# RotaryEncoder_connection.net
KiCad netlist of a schematic drawn in Altium Designer
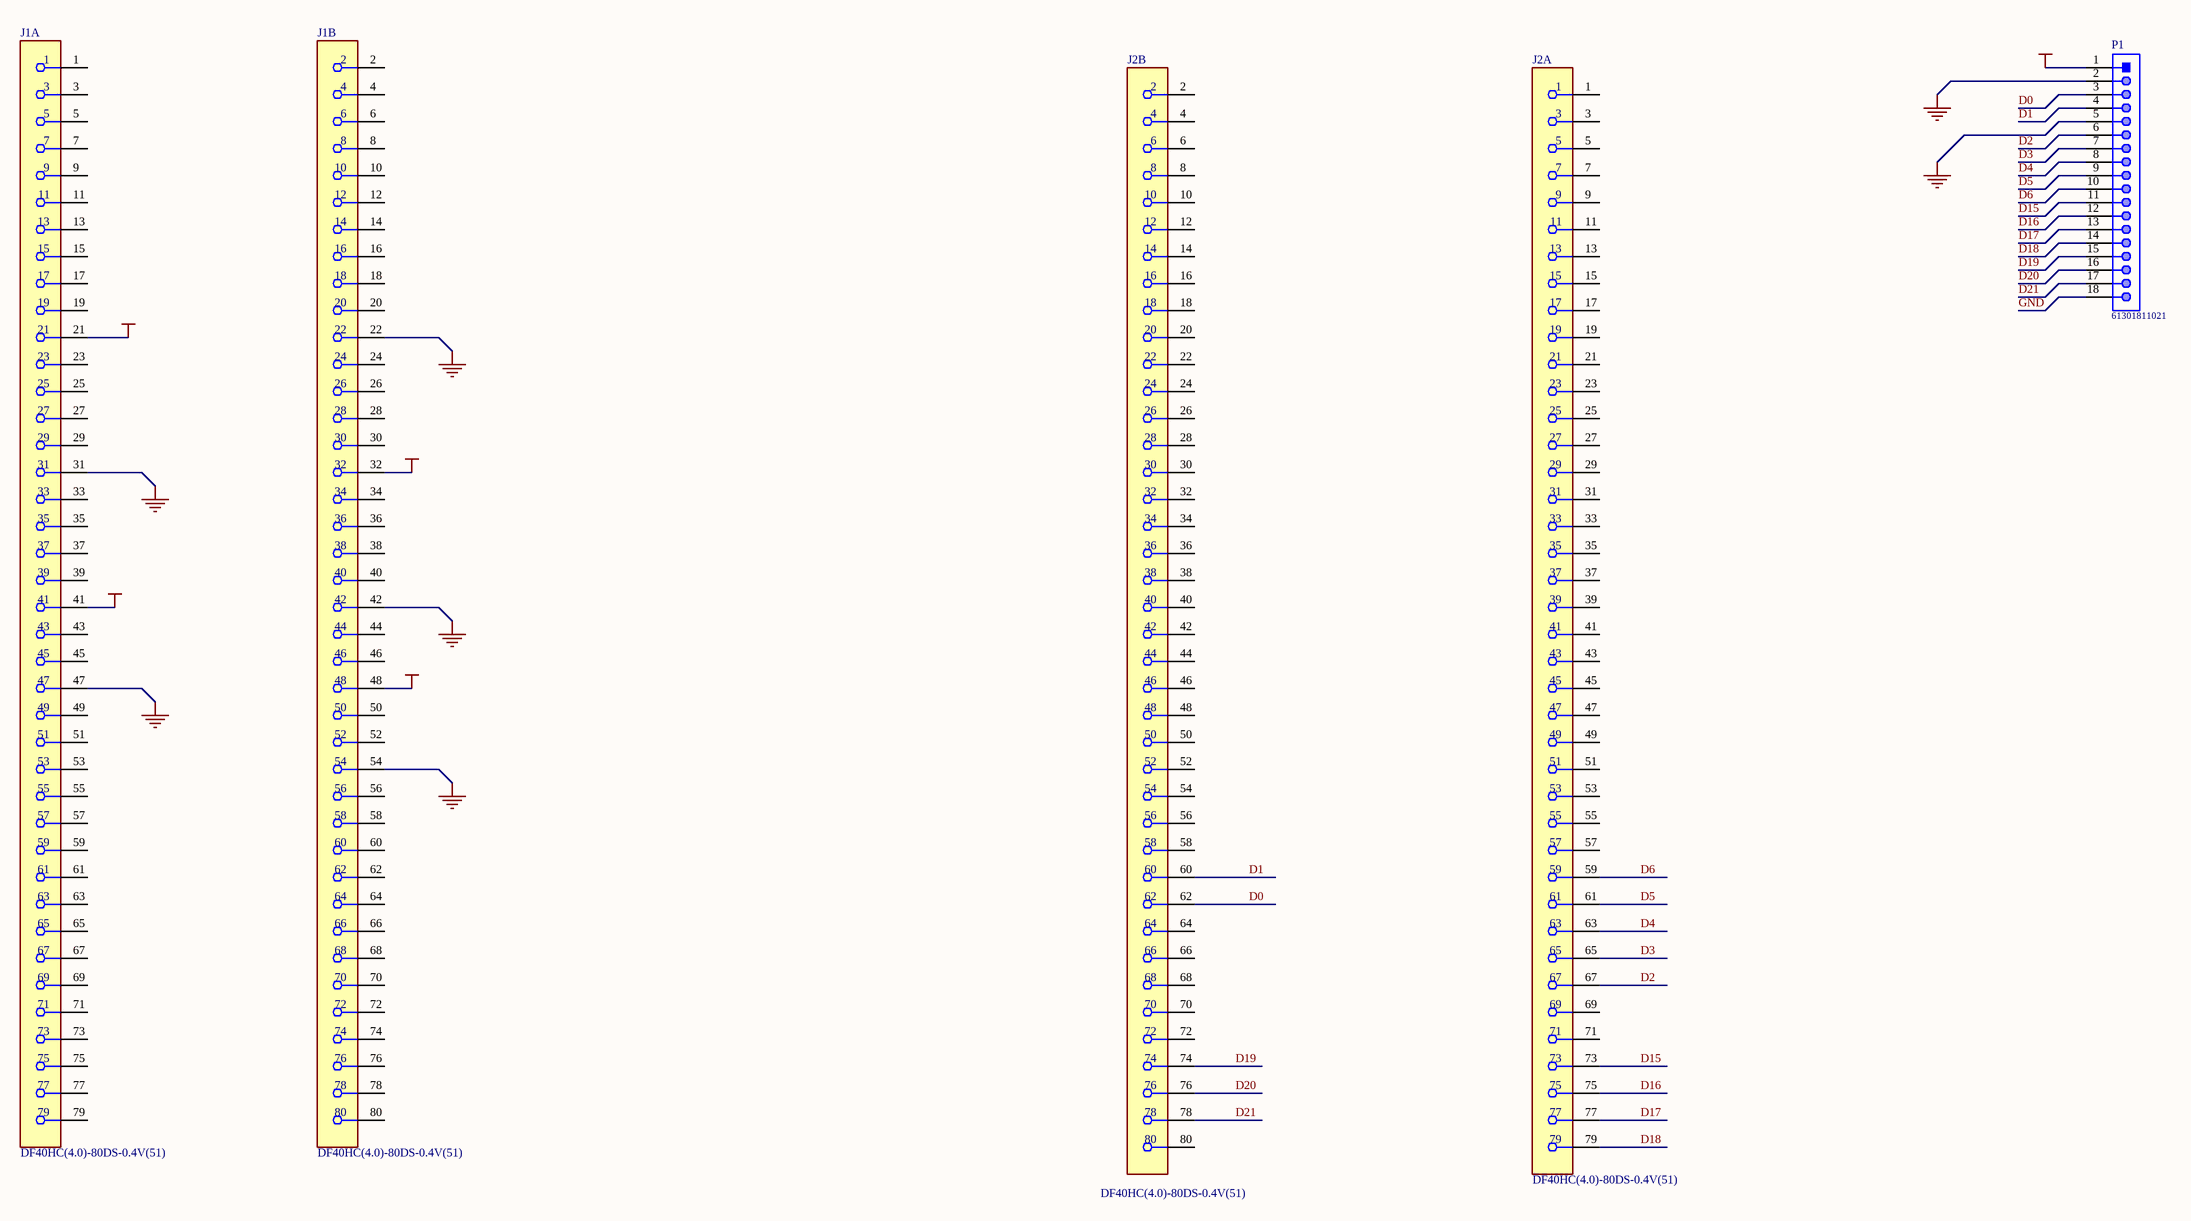
[diagram p0: RotaryEncoder_connection.SchDoc]

(export (version "E")
  (design (tool "Eeschema 10.0.6"))
  (components
    (comp (ref "J1")
      (value "DF40HC(4.0)-80DS-0.4V(51)")
      (footprint "FP-DF40HC_4_0_-80DS-0_4V-MFG")
      (description "CONN RCPT 80POS SMD GOLD")
      (fields
        (field (name "OCTOPART") "https://octopart.com/df40hc%284.0%29-80ds-0.4v%2851%29-hirose-19677719")
        (field (name "MANUFACTURER") "Hirose")
      )
      (libsource (lib "Altium Content Vault") (part "d23b9ca91198f74e05fc9b3cd90b74d"))
    )
    (comp (ref "J2")
      (value "DF40HC(4.0)-80DS-0.4V(51)")
      (footprint "FP-DF40HC_4_0_-80DS-0_4V-MFG")
      (description "CONN RCPT 80POS SMD GOLD")
      (fields
        (field (name "OCTOPART") "https://octopart.com/df40hc%284.0%29-80ds-0.4v%2851%29-hirose-19677719")
        (field (name "MANUFACTURER") "Hirose")
      )
      (libsource (lib "Altium Content Vault") (part "d23b9ca91198f74e05fc9b3cd90b74d"))
    )
    (comp (ref "P1")
      (value "61301811021")
      (footprint "61301811021")
      (description "THT Angled Pin Header WR-PHD, Pitch 2.54 mm, Single Row, 18 pins")
      (fields (field (name "MANUFACTURER") "Wurth Elektronik") (field (name "PUBLISHER") "WurthElektronik"))
      (libsource (lib "Altium Content Vault") (part "WE-CN-1P-M-R18"))
    )
  )
  (nets
    (net (code "1") (name "+5") (class "Default")
      (node (ref "J1") (pin "21") (pinfunction "21_21") (pintype "passive"))
      (node (ref "J1") (pin "32") (pinfunction "32_32") (pintype "passive"))
      (node (ref "J1") (pin "41") (pinfunction "41_41") (pintype "passive"))
      (node (ref "J1") (pin "48") (pinfunction "48_48") (pintype "passive"))
      (node (ref "P1") (pin "1") (pinfunction "1_1") (pintype "passive"))
    )
    (net (code "2") (name "/D0") (class "Default")
      (node (ref "J2") (pin "62") (pinfunction "62_62") (pintype "passive"))
      (node (ref "P1") (pin "3") (pinfunction "3_3") (pintype "passive"))
    )
    (net (code "3") (name "/D1") (class "Default")
      (node (ref "J2") (pin "60") (pinfunction "60_60") (pintype "passive"))
      (node (ref "P1") (pin "4") (pinfunction "4_4") (pintype "passive"))
    )
    (net (code "4") (name "/D2") (class "Default")
      (node (ref "J2") (pin "67") (pinfunction "67_67") (pintype "passive"))
      (node (ref "P1") (pin "6") (pinfunction "6_6") (pintype "passive"))
    )
    (net (code "5") (name "/D3") (class "Default")
      (node (ref "J2") (pin "65") (pinfunction "65_65") (pintype "passive"))
      (node (ref "P1") (pin "7") (pinfunction "7_7") (pintype "passive"))
    )
    (net (code "6") (name "/D4") (class "Default")
      (node (ref "J2") (pin "63") (pinfunction "63_63") (pintype "passive"))
      (node (ref "P1") (pin "8") (pinfunction "8_8") (pintype "passive"))
    )
    (net (code "7") (name "/D5") (class "Default")
      (node (ref "J2") (pin "61") (pinfunction "61_61") (pintype "passive"))
      (node (ref "P1") (pin "9") (pinfunction "9_9") (pintype "passive"))
    )
    (net (code "8") (name "/D6") (class "Default")
      (node (ref "J2") (pin "59") (pinfunction "59_59") (pintype "passive"))
      (node (ref "P1") (pin "10") (pinfunction "10_10") (pintype "passive"))
    )
    (net (code "9") (name "/D15") (class "Default")
      (node (ref "J2") (pin "73") (pinfunction "73_73") (pintype "passive"))
      (node (ref "P1") (pin "11") (pinfunction "11_11") (pintype "passive"))
    )
    (net (code "10") (name "/D16") (class "Default")
      (node (ref "J2") (pin "75") (pinfunction "75_75") (pintype "passive"))
      (node (ref "P1") (pin "12") (pinfunction "12_12") (pintype "passive"))
    )
    (net (code "11") (name "/D17") (class "Default")
      (node (ref "J2") (pin "77") (pinfunction "77_77") (pintype "passive"))
      (node (ref "P1") (pin "13") (pinfunction "13_13") (pintype "passive"))
    )
    (net (code "12") (name "/D18") (class "Default")
      (node (ref "J2") (pin "79") (pinfunction "79_79") (pintype "passive"))
      (node (ref "P1") (pin "14") (pinfunction "14_14") (pintype "passive"))
    )
    (net (code "13") (name "/D19") (class "Default")
      (node (ref "J2") (pin "74") (pinfunction "74_74") (pintype "passive"))
      (node (ref "P1") (pin "15") (pinfunction "15_15") (pintype "passive"))
    )
    (net (code "14") (name "/D20") (class "Default")
      (node (ref "J2") (pin "76") (pinfunction "76_76") (pintype "passive"))
      (node (ref "P1") (pin "16") (pinfunction "16_16") (pintype "passive"))
    )
    (net (code "15") (name "/D21") (class "Default")
      (node (ref "J2") (pin "78") (pinfunction "78_78") (pintype "passive"))
      (node (ref "P1") (pin "17") (pinfunction "17_17") (pintype "passive"))
    )
    (net (code "16") (name "GND") (class "Default")
      (node (ref "J1") (pin "22") (pinfunction "22_22") (pintype "passive"))
      (node (ref "J1") (pin "31") (pinfunction "31_31") (pintype "passive"))
      (node (ref "J1") (pin "42") (pinfunction "42_42") (pintype "passive"))
      (node (ref "J1") (pin "47") (pinfunction "47_47") (pintype "passive"))
      (node (ref "J1") (pin "54") (pinfunction "54_54") (pintype "passive"))
      (node (ref "P1") (pin "18") (pinfunction "18_18") (pintype "passive"))
      (node (ref "P1") (pin "2") (pinfunction "2_2") (pintype "passive"))
      (node (ref "P1") (pin "5") (pinfunction "5_5") (pintype "passive"))
    )
    (net (code "17") (name "unconnected-(J1-Pad1)") (class "Default")
      (node (ref "J1") (pin "1") (pinfunction "1_1") (pintype "passive"))
    )
    (net (code "18") (name "unconnected-(J1-Pad2)") (class "Default")
      (node (ref "J1") (pin "2") (pinfunction "2_2") (pintype "passive"))
    )
    (net (code "19") (name "unconnected-(J1-Pad3)") (class "Default")
      (node (ref "J1") (pin "3") (pinfunction "3_3") (pintype "passive"))
    )
    (net (code "20") (name "unconnected-(J1-Pad4)") (class "Default")
      (node (ref "J1") (pin "4") (pinfunction "4_4") (pintype "passive"))
    )
    (net (code "21") (name "unconnected-(J1-Pad5)") (class "Default")
      (node (ref "J1") (pin "5") (pinfunction "5_5") (pintype "passive"))
    )
    (net (code "22") (name "unconnected-(J1-Pad6)") (class "Default")
      (node (ref "J1") (pin "6") (pinfunction "6_6") (pintype "passive"))
    )
    (net (code "23") (name "unconnected-(J1-Pad7)") (class "Default")
      (node (ref "J1") (pin "7") (pinfunction "7_7") (pintype "passive"))
    )
    (net (code "24") (name "unconnected-(J1-Pad8)") (class "Default")
      (node (ref "J1") (pin "8") (pinfunction "8_8") (pintype "passive"))
    )
    (net (code "25") (name "unconnected-(J1-Pad9)") (class "Default")
      (node (ref "J1") (pin "9") (pinfunction "9_9") (pintype "passive"))
    )
    (net (code "26") (name "unconnected-(J1-Pad10)") (class "Default")
      (node (ref "J1") (pin "10") (pinfunction "10_10") (pintype "passive"))
    )
    (net (code "27") (name "unconnected-(J1-Pad11)") (class "Default")
      (node (ref "J1") (pin "11") (pinfunction "11_11") (pintype "passive"))
    )
    (net (code "28") (name "unconnected-(J1-Pad12)") (class "Default")
      (node (ref "J1") (pin "12") (pinfunction "12_12") (pintype "passive"))
    )
    (net (code "29") (name "unconnected-(J1-Pad13)") (class "Default")
      (node (ref "J1") (pin "13") (pinfunction "13_13") (pintype "passive"))
    )
    (net (code "30") (name "unconnected-(J1-Pad14)") (class "Default")
      (node (ref "J1") (pin "14") (pinfunction "14_14") (pintype "passive"))
    )
    (net (code "31") (name "unconnected-(J1-Pad15)") (class "Default")
      (node (ref "J1") (pin "15") (pinfunction "15_15") (pintype "passive"))
    )
    (net (code "32") (name "unconnected-(J1-Pad16)") (class "Default")
      (node (ref "J1") (pin "16") (pinfunction "16_16") (pintype "passive"))
    )
    (net (code "33") (name "unconnected-(J1-Pad17)") (class "Default")
      (node (ref "J1") (pin "17") (pinfunction "17_17") (pintype "passive"))
    )
    (net (code "34") (name "unconnected-(J1-Pad18)") (class "Default")
      (node (ref "J1") (pin "18") (pinfunction "18_18") (pintype "passive"))
    )
    (net (code "35") (name "unconnected-(J1-Pad19)") (class "Default")
      (node (ref "J1") (pin "19") (pinfunction "19_19") (pintype "passive"))
    )
    (net (code "36") (name "unconnected-(J1-Pad20)") (class "Default")
      (node (ref "J1") (pin "20") (pinfunction "20_20") (pintype "passive"))
    )
    (net (code "37") (name "unconnected-(J1-Pad23)") (class "Default")
      (node (ref "J1") (pin "23") (pinfunction "23_23") (pintype "passive"))
    )
    (net (code "38") (name "unconnected-(J1-Pad24)") (class "Default")
      (node (ref "J1") (pin "24") (pinfunction "24_24") (pintype "passive"))
    )
    (net (code "39") (name "unconnected-(J1-Pad25)") (class "Default")
      (node (ref "J1") (pin "25") (pinfunction "25_25") (pintype "passive"))
    )
    (net (code "40") (name "unconnected-(J1-Pad26)") (class "Default")
      (node (ref "J1") (pin "26") (pinfunction "26_26") (pintype "passive"))
    )
    (net (code "41") (name "unconnected-(J1-Pad27)") (class "Default")
      (node (ref "J1") (pin "27") (pinfunction "27_27") (pintype "passive"))
    )
    (net (code "42") (name "unconnected-(J1-Pad28)") (class "Default")
      (node (ref "J1") (pin "28") (pinfunction "28_28") (pintype "passive"))
    )
    (net (code "43") (name "unconnected-(J1-Pad29)") (class "Default")
      (node (ref "J1") (pin "29") (pinfunction "29_29") (pintype "passive"))
    )
    (net (code "44") (name "unconnected-(J1-Pad30)") (class "Default")
      (node (ref "J1") (pin "30") (pinfunction "30_30") (pintype "passive"))
    )
    (net (code "45") (name "unconnected-(J1-Pad33)") (class "Default")
      (node (ref "J1") (pin "33") (pinfunction "33_33") (pintype "passive"))
    )
    (net (code "46") (name "unconnected-(J1-Pad34)") (class "Default")
      (node (ref "J1") (pin "34") (pinfunction "34_34") (pintype "passive"))
    )
    (net (code "47") (name "unconnected-(J1-Pad35)") (class "Default")
      (node (ref "J1") (pin "35") (pinfunction "35_35") (pintype "passive"))
    )
    (net (code "48") (name "unconnected-(J1-Pad36)") (class "Default")
      (node (ref "J1") (pin "36") (pinfunction "36_36") (pintype "passive"))
    )
    (net (code "49") (name "unconnected-(J1-Pad37)") (class "Default")
      (node (ref "J1") (pin "37") (pinfunction "37_37") (pintype "passive"))
    )
    (net (code "50") (name "unconnected-(J1-Pad38)") (class "Default")
      (node (ref "J1") (pin "38") (pinfunction "38_38") (pintype "passive"))
    )
    (net (code "51") (name "unconnected-(J1-Pad39)") (class "Default")
      (node (ref "J1") (pin "39") (pinfunction "39_39") (pintype "passive"))
    )
    (net (code "52") (name "unconnected-(J1-Pad40)") (class "Default")
      (node (ref "J1") (pin "40") (pinfunction "40_40") (pintype "passive"))
    )
    (net (code "53") (name "unconnected-(J1-Pad43)") (class "Default")
      (node (ref "J1") (pin "43") (pinfunction "43_43") (pintype "passive"))
    )
    (net (code "54") (name "unconnected-(J1-Pad44)") (class "Default")
      (node (ref "J1") (pin "44") (pinfunction "44_44") (pintype "passive"))
    )
    (net (code "55") (name "unconnected-(J1-Pad45)") (class "Default")
      (node (ref "J1") (pin "45") (pinfunction "45_45") (pintype "passive"))
    )
    (net (code "56") (name "unconnected-(J1-Pad46)") (class "Default")
      (node (ref "J1") (pin "46") (pinfunction "46_46") (pintype "passive"))
    )
    (net (code "57") (name "unconnected-(J1-Pad49)") (class "Default")
      (node (ref "J1") (pin "49") (pinfunction "49_49") (pintype "passive"))
    )
    (net (code "58") (name "unconnected-(J1-Pad50)") (class "Default")
      (node (ref "J1") (pin "50") (pinfunction "50_50") (pintype "passive"))
    )
    (net (code "59") (name "unconnected-(J1-Pad51)") (class "Default")
      (node (ref "J1") (pin "51") (pinfunction "51_51") (pintype "passive"))
    )
    (net (code "60") (name "unconnected-(J1-Pad52)") (class "Default")
      (node (ref "J1") (pin "52") (pinfunction "52_52") (pintype "passive"))
    )
    (net (code "61") (name "unconnected-(J1-Pad53)") (class "Default")
      (node (ref "J1") (pin "53") (pinfunction "53_53") (pintype "passive"))
    )
    (net (code "62") (name "unconnected-(J1-Pad55)") (class "Default")
      (node (ref "J1") (pin "55") (pinfunction "55_55") (pintype "passive"))
    )
    (net (code "63") (name "unconnected-(J1-Pad56)") (class "Default")
      (node (ref "J1") (pin "56") (pinfunction "56_56") (pintype "passive"))
    )
    (net (code "64") (name "unconnected-(J1-Pad57)") (class "Default")
      (node (ref "J1") (pin "57") (pinfunction "57_57") (pintype "passive"))
    )
    (net (code "65") (name "unconnected-(J1-Pad58)") (class "Default")
      (node (ref "J1") (pin "58") (pinfunction "58_58") (pintype "passive"))
    )
    (net (code "66") (name "unconnected-(J1-Pad59)") (class "Default")
      (node (ref "J1") (pin "59") (pinfunction "59_59") (pintype "passive"))
    )
    (net (code "67") (name "unconnected-(J1-Pad60)") (class "Default")
      (node (ref "J1") (pin "60") (pinfunction "60_60") (pintype "passive"))
    )
    (net (code "68") (name "unconnected-(J1-Pad61)") (class "Default")
      (node (ref "J1") (pin "61") (pinfunction "61_61") (pintype "passive"))
    )
    (net (code "69") (name "unconnected-(J1-Pad62)") (class "Default")
      (node (ref "J1") (pin "62") (pinfunction "62_62") (pintype "passive"))
    )
    (net (code "70") (name "unconnected-(J1-Pad63)") (class "Default")
      (node (ref "J1") (pin "63") (pinfunction "63_63") (pintype "passive"))
    )
    (net (code "71") (name "unconnected-(J1-Pad64)") (class "Default")
      (node (ref "J1") (pin "64") (pinfunction "64_64") (pintype "passive"))
    )
    (net (code "72") (name "unconnected-(J1-Pad65)") (class "Default")
      (node (ref "J1") (pin "65") (pinfunction "65_65") (pintype "passive"))
    )
    (net (code "73") (name "unconnected-(J1-Pad66)") (class "Default")
      (node (ref "J1") (pin "66") (pinfunction "66_66") (pintype "passive"))
    )
    (net (code "74") (name "unconnected-(J1-Pad67)") (class "Default")
      (node (ref "J1") (pin "67") (pinfunction "67_67") (pintype "passive"))
    )
    (net (code "75") (name "unconnected-(J1-Pad68)") (class "Default")
      (node (ref "J1") (pin "68") (pinfunction "68_68") (pintype "passive"))
    )
    (net (code "76") (name "unconnected-(J1-Pad69)") (class "Default")
      (node (ref "J1") (pin "69") (pinfunction "69_69") (pintype "passive"))
    )
    (net (code "77") (name "unconnected-(J1-Pad70)") (class "Default")
      (node (ref "J1") (pin "70") (pinfunction "70_70") (pintype "passive"))
    )
    (net (code "78") (name "unconnected-(J1-Pad71)") (class "Default")
      (node (ref "J1") (pin "71") (pinfunction "71_71") (pintype "passive"))
    )
    (net (code "79") (name "unconnected-(J1-Pad72)") (class "Default")
      (node (ref "J1") (pin "72") (pinfunction "72_72") (pintype "passive"))
    )
    (net (code "80") (name "unconnected-(J1-Pad73)") (class "Default")
      (node (ref "J1") (pin "73") (pinfunction "73_73") (pintype "passive"))
    )
    (net (code "81") (name "unconnected-(J1-Pad74)") (class "Default")
      (node (ref "J1") (pin "74") (pinfunction "74_74") (pintype "passive"))
    )
    (net (code "82") (name "unconnected-(J1-Pad75)") (class "Default")
      (node (ref "J1") (pin "75") (pinfunction "75_75") (pintype "passive"))
    )
    (net (code "83") (name "unconnected-(J1-Pad76)") (class "Default")
      (node (ref "J1") (pin "76") (pinfunction "76_76") (pintype "passive"))
    )
    (net (code "84") (name "unconnected-(J1-Pad77)") (class "Default")
      (node (ref "J1") (pin "77") (pinfunction "77_77") (pintype "passive"))
    )
    (net (code "85") (name "unconnected-(J1-Pad78)") (class "Default")
      (node (ref "J1") (pin "78") (pinfunction "78_78") (pintype "passive"))
    )
    (net (code "86") (name "unconnected-(J1-Pad79)") (class "Default")
      (node (ref "J1") (pin "79") (pinfunction "79_79") (pintype "passive"))
    )
    (net (code "87") (name "unconnected-(J1-Pad80)") (class "Default")
      (node (ref "J1") (pin "80") (pinfunction "80_80") (pintype "passive"))
    )
    (net (code "88") (name "unconnected-(J2-Pad1)") (class "Default")
      (node (ref "J2") (pin "1") (pinfunction "1_1") (pintype "passive"))
    )
    (net (code "89") (name "unconnected-(J2-Pad2)") (class "Default")
      (node (ref "J2") (pin "2") (pinfunction "2_2") (pintype "passive"))
    )
    (net (code "90") (name "unconnected-(J2-Pad3)") (class "Default")
      (node (ref "J2") (pin "3") (pinfunction "3_3") (pintype "passive"))
    )
    (net (code "91") (name "unconnected-(J2-Pad4)") (class "Default")
      (node (ref "J2") (pin "4") (pinfunction "4_4") (pintype "passive"))
    )
    (net (code "92") (name "unconnected-(J2-Pad5)") (class "Default")
      (node (ref "J2") (pin "5") (pinfunction "5_5") (pintype "passive"))
    )
    (net (code "93") (name "unconnected-(J2-Pad6)") (class "Default")
      (node (ref "J2") (pin "6") (pinfunction "6_6") (pintype "passive"))
    )
    (net (code "94") (name "unconnected-(J2-Pad7)") (class "Default")
      (node (ref "J2") (pin "7") (pinfunction "7_7") (pintype "passive"))
    )
    (net (code "95") (name "unconnected-(J2-Pad8)") (class "Default")
      (node (ref "J2") (pin "8") (pinfunction "8_8") (pintype "passive"))
    )
    (net (code "96") (name "unconnected-(J2-Pad9)") (class "Default")
      (node (ref "J2") (pin "9") (pinfunction "9_9") (pintype "passive"))
    )
    (net (code "97") (name "unconnected-(J2-Pad10)") (class "Default")
      (node (ref "J2") (pin "10") (pinfunction "10_10") (pintype "passive"))
    )
    (net (code "98") (name "unconnected-(J2-Pad11)") (class "Default")
      (node (ref "J2") (pin "11") (pinfunction "11_11") (pintype "passive"))
    )
    (net (code "99") (name "unconnected-(J2-Pad12)") (class "Default")
      (node (ref "J2") (pin "12") (pinfunction "12_12") (pintype "passive"))
    )
    (net (code "100") (name "unconnected-(J2-Pad13)") (class "Default")
      (node (ref "J2") (pin "13") (pinfunction "13_13") (pintype "passive"))
    )
    (net (code "101") (name "unconnected-(J2-Pad14)") (class "Default")
      (node (ref "J2") (pin "14") (pinfunction "14_14") (pintype "passive"))
    )
    (net (code "102") (name "unconnected-(J2-Pad15)") (class "Default")
      (node (ref "J2") (pin "15") (pinfunction "15_15") (pintype "passive"))
    )
    (net (code "103") (name "unconnected-(J2-Pad16)") (class "Default")
      (node (ref "J2") (pin "16") (pinfunction "16_16") (pintype "passive"))
    )
    (net (code "104") (name "unconnected-(J2-Pad17)") (class "Default")
      (node (ref "J2") (pin "17") (pinfunction "17_17") (pintype "passive"))
    )
    (net (code "105") (name "unconnected-(J2-Pad18)") (class "Default")
      (node (ref "J2") (pin "18") (pinfunction "18_18") (pintype "passive"))
    )
    (net (code "106") (name "unconnected-(J2-Pad19)") (class "Default")
      (node (ref "J2") (pin "19") (pinfunction "19_19") (pintype "passive"))
    )
    (net (code "107") (name "unconnected-(J2-Pad20)") (class "Default")
      (node (ref "J2") (pin "20") (pinfunction "20_20") (pintype "passive"))
    )
    (net (code "108") (name "unconnected-(J2-Pad21)") (class "Default")
      (node (ref "J2") (pin "21") (pinfunction "21_21") (pintype "passive"))
    )
    (net (code "109") (name "unconnected-(J2-Pad22)") (class "Default")
      (node (ref "J2") (pin "22") (pinfunction "22_22") (pintype "passive"))
    )
    (net (code "110") (name "unconnected-(J2-Pad23)") (class "Default")
      (node (ref "J2") (pin "23") (pinfunction "23_23") (pintype "passive"))
    )
    (net (code "111") (name "unconnected-(J2-Pad24)") (class "Default")
      (node (ref "J2") (pin "24") (pinfunction "24_24") (pintype "passive"))
    )
    (net (code "112") (name "unconnected-(J2-Pad25)") (class "Default")
      (node (ref "J2") (pin "25") (pinfunction "25_25") (pintype "passive"))
    )
    (net (code "113") (name "unconnected-(J2-Pad26)") (class "Default")
      (node (ref "J2") (pin "26") (pinfunction "26_26") (pintype "passive"))
    )
    (net (code "114") (name "unconnected-(J2-Pad27)") (class "Default")
      (node (ref "J2") (pin "27") (pinfunction "27_27") (pintype "passive"))
    )
    (net (code "115") (name "unconnected-(J2-Pad28)") (class "Default")
      (node (ref "J2") (pin "28") (pinfunction "28_28") (pintype "passive"))
    )
    (net (code "116") (name "unconnected-(J2-Pad29)") (class "Default")
      (node (ref "J2") (pin "29") (pinfunction "29_29") (pintype "passive"))
    )
    (net (code "117") (name "unconnected-(J2-Pad30)") (class "Default")
      (node (ref "J2") (pin "30") (pinfunction "30_30") (pintype "passive"))
    )
    (net (code "118") (name "unconnected-(J2-Pad31)") (class "Default")
      (node (ref "J2") (pin "31") (pinfunction "31_31") (pintype "passive"))
    )
    (net (code "119") (name "unconnected-(J2-Pad32)") (class "Default")
      (node (ref "J2") (pin "32") (pinfunction "32_32") (pintype "passive"))
    )
    (net (code "120") (name "unconnected-(J2-Pad33)") (class "Default")
      (node (ref "J2") (pin "33") (pinfunction "33_33") (pintype "passive"))
    )
    (net (code "121") (name "unconnected-(J2-Pad34)") (class "Default")
      (node (ref "J2") (pin "34") (pinfunction "34_34") (pintype "passive"))
    )
    (net (code "122") (name "unconnected-(J2-Pad35)") (class "Default")
      (node (ref "J2") (pin "35") (pinfunction "35_35") (pintype "passive"))
    )
    (net (code "123") (name "unconnected-(J2-Pad36)") (class "Default")
      (node (ref "J2") (pin "36") (pinfunction "36_36") (pintype "passive"))
    )
    (net (code "124") (name "unconnected-(J2-Pad37)") (class "Default")
      (node (ref "J2") (pin "37") (pinfunction "37_37") (pintype "passive"))
    )
    (net (code "125") (name "unconnected-(J2-Pad38)") (class "Default")
      (node (ref "J2") (pin "38") (pinfunction "38_38") (pintype "passive"))
    )
    (net (code "126") (name "unconnected-(J2-Pad39)") (class "Default")
      (node (ref "J2") (pin "39") (pinfunction "39_39") (pintype "passive"))
    )
    (net (code "127") (name "unconnected-(J2-Pad40)") (class "Default")
      (node (ref "J2") (pin "40") (pinfunction "40_40") (pintype "passive"))
    )
    (net (code "128") (name "unconnected-(J2-Pad41)") (class "Default")
      (node (ref "J2") (pin "41") (pinfunction "41_41") (pintype "passive"))
    )
    (net (code "129") (name "unconnected-(J2-Pad42)") (class "Default")
      (node (ref "J2") (pin "42") (pinfunction "42_42") (pintype "passive"))
    )
    (net (code "130") (name "unconnected-(J2-Pad43)") (class "Default")
      (node (ref "J2") (pin "43") (pinfunction "43_43") (pintype "passive"))
    )
    (net (code "131") (name "unconnected-(J2-Pad44)") (class "Default")
      (node (ref "J2") (pin "44") (pinfunction "44_44") (pintype "passive"))
    )
    (net (code "132") (name "unconnected-(J2-Pad45)") (class "Default")
      (node (ref "J2") (pin "45") (pinfunction "45_45") (pintype "passive"))
    )
    (net (code "133") (name "unconnected-(J2-Pad46)") (class "Default")
      (node (ref "J2") (pin "46") (pinfunction "46_46") (pintype "passive"))
    )
    (net (code "134") (name "unconnected-(J2-Pad47)") (class "Default")
      (node (ref "J2") (pin "47") (pinfunction "47_47") (pintype "passive"))
    )
    (net (code "135") (name "unconnected-(J2-Pad48)") (class "Default")
      (node (ref "J2") (pin "48") (pinfunction "48_48") (pintype "passive"))
    )
    (net (code "136") (name "unconnected-(J2-Pad49)") (class "Default")
      (node (ref "J2") (pin "49") (pinfunction "49_49") (pintype "passive"))
    )
    (net (code "137") (name "unconnected-(J2-Pad50)") (class "Default")
      (node (ref "J2") (pin "50") (pinfunction "50_50") (pintype "passive"))
    )
    (net (code "138") (name "unconnected-(J2-Pad51)") (class "Default")
      (node (ref "J2") (pin "51") (pinfunction "51_51") (pintype "passive"))
    )
    (net (code "139") (name "unconnected-(J2-Pad52)") (class "Default")
      (node (ref "J2") (pin "52") (pinfunction "52_52") (pintype "passive"))
    )
    (net (code "140") (name "unconnected-(J2-Pad53)") (class "Default")
      (node (ref "J2") (pin "53") (pinfunction "53_53") (pintype "passive"))
    )
    (net (code "141") (name "unconnected-(J2-Pad54)") (class "Default")
      (node (ref "J2") (pin "54") (pinfunction "54_54") (pintype "passive"))
    )
    (net (code "142") (name "unconnected-(J2-Pad55)") (class "Default")
      (node (ref "J2") (pin "55") (pinfunction "55_55") (pintype "passive"))
    )
    (net (code "143") (name "unconnected-(J2-Pad56)") (class "Default")
      (node (ref "J2") (pin "56") (pinfunction "56_56") (pintype "passive"))
    )
    (net (code "144") (name "unconnected-(J2-Pad57)") (class "Default")
      (node (ref "J2") (pin "57") (pinfunction "57_57") (pintype "passive"))
    )
    (net (code "145") (name "unconnected-(J2-Pad58)") (class "Default")
      (node (ref "J2") (pin "58") (pinfunction "58_58") (pintype "passive"))
    )
    (net (code "146") (name "unconnected-(J2-Pad64)") (class "Default")
      (node (ref "J2") (pin "64") (pinfunction "64_64") (pintype "passive"))
    )
    (net (code "147") (name "unconnected-(J2-Pad66)") (class "Default")
      (node (ref "J2") (pin "66") (pinfunction "66_66") (pintype "passive"))
    )
    (net (code "148") (name "unconnected-(J2-Pad68)") (class "Default")
      (node (ref "J2") (pin "68") (pinfunction "68_68") (pintype "passive"))
    )
    (net (code "149") (name "unconnected-(J2-Pad69)") (class "Default")
      (node (ref "J2") (pin "69") (pinfunction "69_69") (pintype "passive"))
    )
    (net (code "150") (name "unconnected-(J2-Pad70)") (class "Default")
      (node (ref "J2") (pin "70") (pinfunction "70_70") (pintype "passive"))
    )
    (net (code "151") (name "unconnected-(J2-Pad71)") (class "Default")
      (node (ref "J2") (pin "71") (pinfunction "71_71") (pintype "passive"))
    )
    (net (code "152") (name "unconnected-(J2-Pad72)") (class "Default")
      (node (ref "J2") (pin "72") (pinfunction "72_72") (pintype "passive"))
    )
    (net (code "153") (name "unconnected-(J2-Pad80)") (class "Default")
      (node (ref "J2") (pin "80") (pinfunction "80_80") (pintype "passive"))
    )
  )
)
